# PCB_RGBlimp-Q_Subplate.net
KiCad netlist of a schematic drawn in Altium Designer
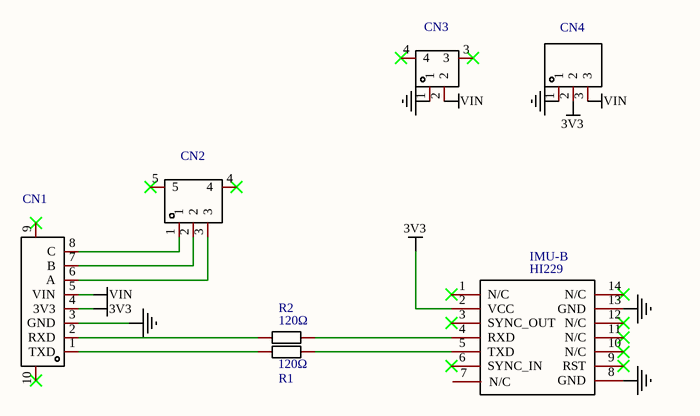
[diagram p0: PCB_RGBlimp-Q_Subplate.schdoc]

(export (version "E")
  (design (tool "Eeschema 10.0.6"))
  (components
    (comp (ref "CN1")
      (value "AFC12-S08CCC-00")
      (fields (field (name "MANUFACTURER") "JS(钜硕电子)"))
      (libsource (lib "altium-import") (part "root_2_AFC12-S08CCC-00_"))
    )
    (comp (ref "CN2")
      (value "AFC12-S03CCC-00")
      (fields (field (name "MANUFACTURER") "JS(钜硕电子)"))
      (libsource (lib "altium-import") (part "root_1_AFC12-S03CCC-00_"))
    )
    (comp (ref "CN3")
      (value "AFC12-S02CCC-00")
      (fields (field (name "MANUFACTURER") "JS(钜硕电子)"))
      (libsource (lib "altium-import") (part "root_1_AFC12-S02CCC-00_"))
    )
    (comp (ref "CN4")
      (value "A2005WV-3P")
      (fields (field (name "MANUFACTURER") "CJT(长江连接器)"))
      (libsource (lib "altium-import") (part "root_1_A2005WV-3P_"))
    )
    (comp (ref "IMU-B")
      (value "HI229")
      (fields (field (name "NAME") "HI229"))
      (libsource (lib "altium-import") (part "root_0_HI229_"))
    )
    (comp (ref "R1")
      (value "120Ω")
      (fields
        (field (name "NAME") "120Ω")
        (field (name "MANUFACTURER") "UNI-ROYAL(厚声)")
        (field (name "MANUFACTURER PART") "0603WAF1200T5E")
      )
      (libsource (lib "altium-import") (part "root_0_120Ω_"))
    )
    (comp (ref "R2")
      (value "120Ω")
      (fields
        (field (name "NAME") "120Ω")
        (field (name "MANUFACTURER") "UNI-ROYAL(厚声)")
        (field (name "MANUFACTURER PART") "0603WAF1200T5E")
      )
      (libsource (lib "altium-import") (part "root_0_120Ω_"))
    )
  )
  (nets
    (net (code "1") (name "3V3") (class "Default")
      (node (ref "CN1") (pin "4") (pinfunction "3V3_4") (pintype "passive"))
      (node (ref "CN4") (pin "2") (pinfunction "2_2") (pintype "passive"))
      (node (ref "IMU-B") (pin "2") (pinfunction "VCC_2") (pintype "passive"))
    )
    (net (code "2") (name "GND") (class "Default")
      (node (ref "CN1") (pin "3") (pinfunction "GND_3") (pintype "passive"))
      (node (ref "CN3") (pin "1") (pinfunction "1_1") (pintype "passive"))
      (node (ref "CN4") (pin "1") (pinfunction "1_1") (pintype "passive"))
      (node (ref "IMU-B") (pin "13") (pinfunction "GND_13") (pintype "passive"))
      (node (ref "IMU-B") (pin "8") (pinfunction "GND_8") (pintype "passive"))
    )
    (net (code "3") (name "Net-(CN1-A)") (class "Default")
      (node (ref "CN1") (pin "6") (pinfunction "A_6") (pintype "passive"))
      (node (ref "CN2") (pin "3") (pinfunction "3_3") (pintype "passive"))
    )
    (net (code "4") (name "Net-(CN1-B)") (class "Default")
      (node (ref "CN1") (pin "7") (pinfunction "B_7") (pintype "passive"))
      (node (ref "CN2") (pin "2") (pinfunction "2_2") (pintype "passive"))
    )
    (net (code "5") (name "Net-(CN1-C)") (class "Default")
      (node (ref "CN1") (pin "8") (pinfunction "C_8") (pintype "passive"))
      (node (ref "CN2") (pin "1") (pinfunction "1_1") (pintype "passive"))
    )
    (net (code "6") (name "Net-(CN1-RXD)") (class "Default")
      (node (ref "CN1") (pin "2") (pinfunction "RXD_2") (pintype "passive"))
      (node (ref "R2") (pin "1") (pinfunction "1_1") (pintype "passive"))
    )
    (net (code "7") (name "Net-(CN1-TXD)") (class "Default")
      (node (ref "CN1") (pin "1") (pinfunction "TXD_1") (pintype "passive"))
      (node (ref "R1") (pin "1") (pinfunction "1_1") (pintype "passive"))
    )
    (net (code "8") (name "Net-(IMU-B-RXD)") (class "Default")
      (node (ref "IMU-B") (pin "4") (pinfunction "RXD_4") (pintype "passive"))
      (node (ref "R2") (pin "2") (pinfunction "2_2") (pintype "passive"))
    )
    (net (code "9") (name "Net-(IMU-B-TXD)") (class "Default")
      (node (ref "IMU-B") (pin "5") (pinfunction "TXD_5") (pintype "passive"))
      (node (ref "R1") (pin "2") (pinfunction "2_2") (pintype "passive"))
    )
    (net (code "10") (name "VIN") (class "Default")
      (node (ref "CN1") (pin "5") (pinfunction "VIN_5") (pintype "passive"))
      (node (ref "CN3") (pin "2") (pinfunction "2_2") (pintype "passive"))
      (node (ref "CN4") (pin "3") (pinfunction "3_3") (pintype "passive"))
    )
    (net (code "11") (name "unconnected-(CN1-Pad9)") (class "Default")
      (node (ref "CN1") (pin "9") (pinfunction "9_9") (pintype "passive+no_connect"))
    )
    (net (code "12") (name "unconnected-(CN1-Pad10)") (class "Default")
      (node (ref "CN1") (pin "10") (pinfunction "10_10") (pintype "passive+no_connect"))
    )
    (net (code "13") (name "unconnected-(CN2-Pad4)") (class "Default")
      (node (ref "CN2") (pin "4") (pinfunction "4_4") (pintype "passive+no_connect"))
    )
    (net (code "14") (name "unconnected-(CN2-Pad5)") (class "Default")
      (node (ref "CN2") (pin "5") (pinfunction "5_5") (pintype "passive+no_connect"))
    )
    (net (code "15") (name "unconnected-(CN3-Pad3)") (class "Default")
      (node (ref "CN3") (pin "3") (pinfunction "3_3") (pintype "passive+no_connect"))
    )
    (net (code "16") (name "unconnected-(CN3-Pad4)") (class "Default")
      (node (ref "CN3") (pin "4") (pinfunction "4_4") (pintype "passive+no_connect"))
    )
    (net (code "17") (name "unconnected-(IMU-B-N{slash}C-Pad1)") (class "Default")
      (node (ref "IMU-B") (pin "1") (pinfunction "N/C_1") (pintype "passive+no_connect"))
    )
    (net (code "18") (name "unconnected-(IMU-B-N{slash}C-Pad7)") (class "Default")
      (node (ref "IMU-B") (pin "7") (pinfunction "N/C_7") (pintype "passive"))
    )
    (net (code "19") (name "unconnected-(IMU-B-N{slash}C-Pad10)") (class "Default")
      (node (ref "IMU-B") (pin "10") (pinfunction "N/C_10") (pintype "passive+no_connect"))
    )
    (net (code "20") (name "unconnected-(IMU-B-N{slash}C-Pad11)") (class "Default")
      (node (ref "IMU-B") (pin "11") (pinfunction "N/C_11") (pintype "passive+no_connect"))
    )
    (net (code "21") (name "unconnected-(IMU-B-N{slash}C-Pad12)") (class "Default")
      (node (ref "IMU-B") (pin "12") (pinfunction "N/C_12") (pintype "passive+no_connect"))
    )
    (net (code "22") (name "unconnected-(IMU-B-N{slash}C-Pad14)") (class "Default")
      (node (ref "IMU-B") (pin "14") (pinfunction "N/C_14") (pintype "passive+no_connect"))
    )
    (net (code "23") (name "unconnected-(IMU-B-RST-Pad9)") (class "Default")
      (node (ref "IMU-B") (pin "9") (pinfunction "RST_9") (pintype "passive+no_connect"))
    )
    (net (code "24") (name "unconnected-(IMU-B-SYNC_IN-Pad6)") (class "Default")
      (node (ref "IMU-B") (pin "6") (pinfunction "SYNC_IN_6") (pintype "passive+no_connect"))
    )
    (net (code "25") (name "unconnected-(IMU-B-SYNC_OUT-Pad3)") (class "Default")
      (node (ref "IMU-B") (pin "3") (pinfunction "SYNC_OUT_3") (pintype "passive+no_connect"))
    )
  )
)
